# alarmclock6.net
KiCad netlist of a schematic drawn in EAGLE
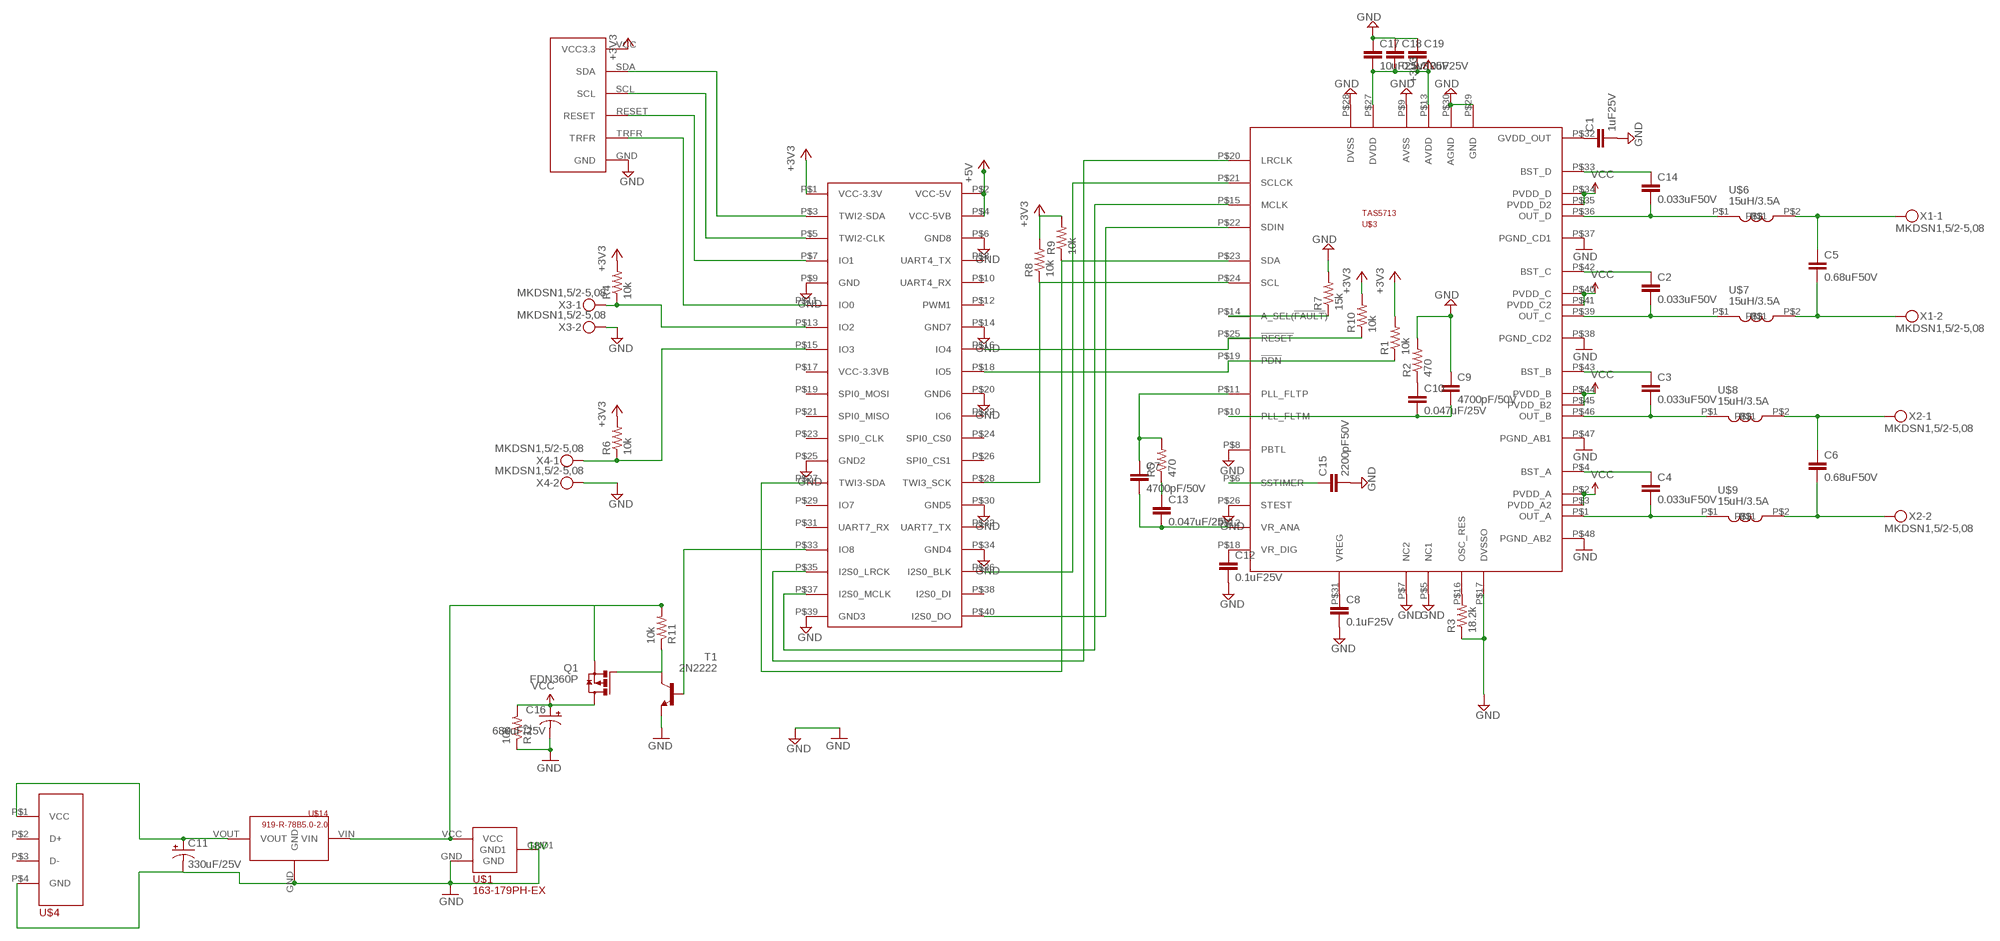
[diagram p0: schematic, sheet 1]

(export (version "E")
  (design (tool "Eeschema 10.0.6"))
  (components
    (comp (ref "C1")
      (value "1uF25V")
      (footprint "eagle-import:0603-CAP")
      (libsource (lib "eagle-import") (part "CAP0603-CAP"))
    )
    (comp (ref "C2")
      (value "0.033uF50V")
      (footprint "eagle-import:0603-CAP")
      (libsource (lib "eagle-import") (part "CAP0603-CAP"))
    )
    (comp (ref "C3")
      (value "0.033uF50V")
      (footprint "eagle-import:0603-CAP")
      (libsource (lib "eagle-import") (part "CAP0603-CAP"))
    )
    (comp (ref "C4")
      (value "0.033uF50V")
      (footprint "eagle-import:0603-CAP")
      (libsource (lib "eagle-import") (part "CAP0603-CAP"))
    )
    (comp (ref "C5")
      (value "0.68uF50V")
      (footprint "eagle-import:0603-CAP")
      (libsource (lib "eagle-import") (part "CAP0603-CAP"))
    )
    (comp (ref "C6")
      (value "0.68uF50V")
      (footprint "eagle-import:0603-CAP")
      (libsource (lib "eagle-import") (part "CAP0603-CAP"))
    )
    (comp (ref "C7")
      (value "4700pF/50V")
      (footprint "eagle-import:0603-CAP")
      (libsource (lib "eagle-import") (part "CAP0603-CAP"))
    )
    (comp (ref "C8")
      (value "0.1uF25V")
      (footprint "eagle-import:0603-CAP")
      (libsource (lib "eagle-import") (part "CAP0603-CAP"))
    )
    (comp (ref "C9")
      (value "4700pF/50V")
      (footprint "eagle-import:0603-CAP")
      (libsource (lib "eagle-import") (part "CAP0603-CAP"))
    )
    (comp (ref "C10")
      (value "0.047uF/25V")
      (footprint "eagle-import:0603-CAP")
      (libsource (lib "eagle-import") (part "CAP0603-CAP"))
    )
    (comp (ref "C11")
      (value "330uF/25V")
      (footprint "eagle-import:CPOL-RADIAL-10UF-25V")
      (libsource (lib "eagle-import") (part "CAP_POLPTH2"))
    )
    (comp (ref "C12")
      (value "0.1uF25V")
      (footprint "eagle-import:0603-CAP")
      (libsource (lib "eagle-import") (part "CAP0603-CAP"))
    )
    (comp (ref "C13")
      (value "0.047uF/25V")
      (footprint "eagle-import:0603-CAP")
      (libsource (lib "eagle-import") (part "CAP0603-CAP"))
    )
    (comp (ref "C14")
      (value "0.033uF50V")
      (footprint "eagle-import:0603-CAP")
      (libsource (lib "eagle-import") (part "CAP0603-CAP"))
    )
    (comp (ref "C15")
      (value "2200pF50V")
      (footprint "eagle-import:0603-CAP")
      (libsource (lib "eagle-import") (part "CAP0603-CAP"))
    )
    (comp (ref "C16")
      (value "680uF/25V")
      (footprint "eagle-import:CPOL-RADIAL-10UF-25V")
      (libsource (lib "eagle-import") (part "CAP_POLPTH2"))
    )
    (comp (ref "C17")
      (value "10uF25V")
      (footprint "eagle-import:0603-CAP")
      (libsource (lib "eagle-import") (part "CAP0603-CAP"))
    )
    (comp (ref "C18")
      (value "0.1uF25V")
      (footprint "eagle-import:0603-CAP")
      (libsource (lib "eagle-import") (part "CAP0603-CAP"))
    )
    (comp (ref "C19")
      (value "10uF25V")
      (footprint "eagle-import:0603-CAP")
      (libsource (lib "eagle-import") (part "CAP0603-CAP"))
    )
    (comp (ref "Q1")
      (value "FDN360P")
      (footprint "eagle-import:SUPER-SOT3")
      (libsource (lib "eagle-import") (part "FDN360P"))
    )
    (comp (ref "R1")
      (value "10k")
      (footprint "eagle-import:0603-RES")
      (libsource (lib "eagle-import") (part "RESISTOR0603-RES"))
    )
    (comp (ref "R2")
      (value "470")
      (footprint "eagle-import:0603-RES")
      (libsource (lib "eagle-import") (part "RESISTOR0603-RES"))
    )
    (comp (ref "R3")
      (value "18.2k")
      (footprint "eagle-import:0603-RES")
      (libsource (lib "eagle-import") (part "RESISTOR0603-RES"))
    )
    (comp (ref "R4")
      (value "10k")
      (footprint "eagle-import:0603-RES")
      (libsource (lib "eagle-import") (part "RESISTOR0603-RES"))
    )
    (comp (ref "R5")
      (value "470")
      (footprint "eagle-import:0603-RES")
      (libsource (lib "eagle-import") (part "RESISTOR0603-RES"))
    )
    (comp (ref "R6")
      (value "10k")
      (footprint "eagle-import:0603-RES")
      (libsource (lib "eagle-import") (part "RESISTOR0603-RES"))
    )
    (comp (ref "R7")
      (value "15k")
      (footprint "eagle-import:0603-RES")
      (libsource (lib "eagle-import") (part "RESISTOR0603-RES"))
    )
    (comp (ref "R8")
      (value "10k")
      (footprint "eagle-import:0603-RES")
      (libsource (lib "eagle-import") (part "RESISTOR0603-RES"))
    )
    (comp (ref "R9")
      (value "10k")
      (footprint "eagle-import:0603-RES")
      (libsource (lib "eagle-import") (part "RESISTOR0603-RES"))
    )
    (comp (ref "R10")
      (value "10k")
      (footprint "eagle-import:0603-RES")
      (libsource (lib "eagle-import") (part "RESISTOR0603-RES"))
    )
    (comp (ref "R11")
      (value "10k")
      (footprint "eagle-import:0603-RES")
      (libsource (lib "eagle-import") (part "RESISTOR0603-RES"))
    )
    (comp (ref "R12")
      (value "10k")
      (footprint "eagle-import:0603-RES")
      (libsource (lib "eagle-import") (part "RESISTOR0603-RES"))
    )
    (comp (ref "T1")
      (value "2N2222")
      (footprint "eagle-import:TO18")
      (libsource (lib "eagle-import") (part "2N2222"))
    )
    (comp (ref "U$1")
      (value "163-179PH-EX")
      (footprint "eagle-import:163-179PH-EX_DIM")
      (libsource (lib "eagle-import") (part "163-179PH-EX"))
    )
    (comp (ref "U$3")
      (value "TAS5713")
      (footprint "eagle-import:TAS5713_DIM")
      (libsource (lib "eagle-import") (part "TAS5713"))
    )
    (comp (ref "U$4")
      (value "USB_TYPEA_CONNECTOR")
      (footprint "eagle-import:USB_DIM")
      (libsource (lib "eagle-import") (part "USB_TYPEA_CONNECTOR"))
    )
    (comp (ref "U$5")
      (value "BANANAPRO-CON6")
      (footprint "eagle-import:BANANAPRO-CON6_DIM")
      (libsource (lib "eagle-import") (part "BANANAPRO-CON6"))
    )
    (comp (ref "U$6")
      (value "15uH/3.5A")
      (footprint "eagle-import:MSS1260_DIM")
      (libsource (lib "eagle-import") (part "MSS1260INDUCTOR"))
    )
    (comp (ref "U$7")
      (value "15uH/3.5A")
      (footprint "eagle-import:MSS1260_DIM")
      (libsource (lib "eagle-import") (part "MSS1260INDUCTOR"))
    )
    (comp (ref "U$8")
      (value "15uH/3.5A")
      (footprint "eagle-import:MSS1260_DIM")
      (libsource (lib "eagle-import") (part "MSS1260INDUCTOR"))
    )
    (comp (ref "U$9")
      (value "15uH/3.5A")
      (footprint "eagle-import:MSS1260_DIM")
      (libsource (lib "eagle-import") (part "MSS1260INDUCTOR"))
    )
    (comp (ref "U$10")
      (value "SKYWRITER")
      (footprint "eagle-import:SKYWRITER_DIM")
      (libsource (lib "eagle-import") (part "SKYWRITER"))
    )
    (comp (ref "U$14")
      (value "919-R-78B5.0-2.0")
      (footprint "eagle-import:919-R-78B5.0-2.0_DIM")
      (libsource (lib "eagle-import") (part "919-R-78B5.0-2.0"))
    )
    (comp (ref "X1")
      (value "MKDSN1,5/2-5,08")
      (footprint "eagle-import:MKDSN1,5_2-5,08")
      (libsource (lib "eagle-import") (part "MKDSN1,5/2-5,08"))
    )
    (comp (ref "X2")
      (value "MKDSN1,5/2-5,08")
      (footprint "eagle-import:MKDSN1,5_2-5,08")
      (libsource (lib "eagle-import") (part "MKDSN1,5/2-5,08"))
    )
    (comp (ref "X3")
      (value "MKDSN1,5/2-5,08")
      (footprint "eagle-import:MKDSN1,5_2-5,08")
      (libsource (lib "eagle-import") (part "MKDSN1,5/2-5,08"))
    )
    (comp (ref "X4")
      (value "MKDSN1,5/2-5,08")
      (footprint "eagle-import:MKDSN1,5_2-5,08")
      (libsource (lib "eagle-import") (part "MKDSN1,5/2-5,08"))
    )
  )
  (nets
    (net (code "1") (name "+3V3") (class "Default")
      (node (ref "C17") (pin "2") (pinfunction "2_2") (pintype "passive"))
      (node (ref "C18") (pin "2") (pinfunction "2_2") (pintype "passive"))
      (node (ref "C19") (pin "2") (pinfunction "2_2") (pintype "passive"))
      (node (ref "R1") (pin "2") (pinfunction "2_2") (pintype "passive"))
      (node (ref "R10") (pin "2") (pinfunction "2_2") (pintype "passive"))
      (node (ref "R4") (pin "2") (pinfunction "2_2") (pintype "passive"))
      (node (ref "R6") (pin "2") (pinfunction "2_2") (pintype "passive"))
      (node (ref "R8") (pin "2") (pinfunction "2_2") (pintype "passive"))
      (node (ref "R9") (pin "2") (pinfunction "2_2") (pintype "passive"))
      (node (ref "U$10") (pin "VCC") (pinfunction "VCC3.3_VCC") (pintype "bidirectional"))
      (node (ref "U$3") (pin "P$13") (pinfunction "AVDD_P$13") (pintype "bidirectional"))
      (node (ref "U$3") (pin "P$27") (pinfunction "DVDD_P$27") (pintype "bidirectional"))
      (node (ref "U$5") (pin "P$1") (pinfunction "VCC-3.3V_P$1") (pintype "bidirectional"))
    )
    (net (code "2") (name "+5V") (class "Default")
      (node (ref "U$5") (pin "P$2") (pinfunction "VCC-5V_P$2") (pintype "bidirectional"))
      (node (ref "U$5") (pin "P$4") (pinfunction "VCC-5VB_P$4") (pintype "bidirectional"))
    )
    (net (code "3") (name "GND") (class "Default")
      (node (ref "C1") (pin "2") (pinfunction "2_2") (pintype "passive"))
      (node (ref "C11") (pin "2") (pinfunction "-_2") (pintype "passive"))
      (node (ref "C12") (pin "2") (pinfunction "2_2") (pintype "passive"))
      (node (ref "C15") (pin "2") (pinfunction "2_2") (pintype "passive"))
      (node (ref "C16") (pin "2") (pinfunction "-_2") (pintype "passive"))
      (node (ref "C17") (pin "1") (pinfunction "1_1") (pintype "passive"))
      (node (ref "C18") (pin "1") (pinfunction "1_1") (pintype "passive"))
      (node (ref "C19") (pin "1") (pinfunction "1_1") (pintype "passive"))
      (node (ref "C8") (pin "2") (pinfunction "2_2") (pintype "passive"))
      (node (ref "C9") (pin "1") (pinfunction "1_1") (pintype "passive"))
      (node (ref "R12") (pin "1") (pinfunction "1_1") (pintype "passive"))
      (node (ref "R2") (pin "2") (pinfunction "2_2") (pintype "passive"))
      (node (ref "R3") (pin "1") (pinfunction "1_1") (pintype "passive"))
      (node (ref "R7") (pin "2") (pinfunction "2_2") (pintype "passive"))
      (node (ref "T1") (pin "1") (pinfunction "E_1") (pintype "passive"))
      (node (ref "U$1") (pin "GND") (pinfunction "GND_GND") (pintype "bidirectional"))
      (node (ref "U$1") (pin "GND1") (pinfunction "GND1_GND1") (pintype "bidirectional"))
      (node (ref "U$10") (pin "GND") (pinfunction "GND_GND") (pintype "bidirectional"))
      (node (ref "U$14") (pin "GND") (pinfunction "GND_GND") (pintype "bidirectional"))
      (node (ref "U$3") (pin "P$17") (pinfunction "DVSSO_P$17") (pintype "bidirectional"))
      (node (ref "U$3") (pin "P$26") (pinfunction "STEST_P$26") (pintype "bidirectional"))
      (node (ref "U$3") (pin "P$28") (pinfunction "DVSS_P$28") (pintype "bidirectional"))
      (node (ref "U$3") (pin "P$29") (pinfunction "GND_P$29") (pintype "bidirectional"))
      (node (ref "U$3") (pin "P$30") (pinfunction "AGND_P$30") (pintype "bidirectional"))
      (node (ref "U$3") (pin "P$37") (pinfunction "PGND_CD1_P$37") (pintype "bidirectional"))
      (node (ref "U$3") (pin "P$38") (pinfunction "PGND_CD2_P$38") (pintype "bidirectional"))
      (node (ref "U$3") (pin "P$47") (pinfunction "PGND_AB1_P$47") (pintype "bidirectional"))
      (node (ref "U$3") (pin "P$48") (pinfunction "PGND_AB2_P$48") (pintype "bidirectional"))
      (node (ref "U$3") (pin "P$5") (pinfunction "NC1_P$5") (pintype "bidirectional"))
      (node (ref "U$3") (pin "P$7") (pinfunction "NC2_P$7") (pintype "bidirectional"))
      (node (ref "U$3") (pin "P$8") (pinfunction "PBTL_P$8") (pintype "bidirectional"))
      (node (ref "U$3") (pin "P$9") (pinfunction "AVSS_P$9") (pintype "bidirectional"))
      (node (ref "U$4") (pin "P$4") (pinfunction "GND_P$4") (pintype "bidirectional"))
      (node (ref "U$5") (pin "P$14") (pinfunction "GND7_P$14") (pintype "bidirectional"))
      (node (ref "U$5") (pin "P$20") (pinfunction "GND6_P$20") (pintype "bidirectional"))
      (node (ref "U$5") (pin "P$25") (pinfunction "GND2_P$25") (pintype "bidirectional"))
      (node (ref "U$5") (pin "P$30") (pinfunction "GND5_P$30") (pintype "bidirectional"))
      (node (ref "U$5") (pin "P$34") (pinfunction "GND4_P$34") (pintype "bidirectional"))
      (node (ref "U$5") (pin "P$39") (pinfunction "GND3_P$39") (pintype "bidirectional"))
      (node (ref "U$5") (pin "P$6") (pinfunction "GND8_P$6") (pintype "bidirectional"))
      (node (ref "U$5") (pin "P$9") (pinfunction "GND_P$9") (pintype "bidirectional"))
      (node (ref "X3") (pin "2") (pinfunction "KL_2") (pintype "passive"))
      (node (ref "X4") (pin "2") (pinfunction "KL_2") (pintype "passive"))
    )
    (net (code "4") (name "Net-(C10-Pad1)") (class "Default")
      (node (ref "C10") (pin "1") (pinfunction "1_1") (pintype "passive"))
      (node (ref "R2") (pin "1") (pinfunction "1_1") (pintype "passive"))
    )
    (net (code "5") (name "Net-(C11-+)") (class "Default")
      (node (ref "C11") (pin "1") (pinfunction "+_1") (pintype "passive"))
      (node (ref "U$14") (pin "VOUT") (pinfunction "VOUT_VOUT") (pintype "bidirectional"))
      (node (ref "U$4") (pin "P$1") (pinfunction "VCC_P$1") (pintype "bidirectional"))
    )
    (net (code "6") (name "Net-(C13-Pad1)") (class "Default")
      (node (ref "C13") (pin "1") (pinfunction "1_1") (pintype "passive"))
      (node (ref "R5") (pin "1") (pinfunction "1_1") (pintype "passive"))
    )
    (net (code "7") (name "Net-(Q1-G)") (class "Default")
      (node (ref "Q1") (pin "1") (pinfunction "G_1") (pintype "passive"))
      (node (ref "R11") (pin "1") (pinfunction "1_1") (pintype "passive"))
      (node (ref "T1") (pin "3") (pinfunction "C_3") (pintype "passive"))
    )
    (net (code "8") (name "Net-(Q1-S)") (class "Default")
      (node (ref "Q1") (pin "2") (pinfunction "S_2") (pintype "passive"))
      (node (ref "R11") (pin "2") (pinfunction "2_2") (pintype "passive"))
      (node (ref "U$1") (pin "VCC") (pinfunction "VCC_VCC") (pintype "bidirectional"))
      (node (ref "U$14") (pin "VIN") (pinfunction "VIN_VIN") (pintype "bidirectional"))
    )
    (net (code "9") (name "Net-(T1-B)") (class "Default")
      (node (ref "T1") (pin "2") (pinfunction "B_2") (pintype "passive"))
      (node (ref "U$5") (pin "P$33") (pinfunction "IO8_P$33") (pintype "bidirectional"))
    )
    (net (code "10") (name "Net-(U$3-A_SEL(~{FAULT}))") (class "Default")
      (node (ref "R7") (pin "1") (pinfunction "1_1") (pintype "passive"))
      (node (ref "U$3") (pin "P$14") (pinfunction "A_SEL(~{FAULT})_P$14") (pintype "bidirectional"))
    )
    (net (code "11") (name "Net-(U$3-BST_A)") (class "Default")
      (node (ref "C4") (pin "1") (pinfunction "1_1") (pintype "passive"))
      (node (ref "U$3") (pin "P$4") (pinfunction "BST_A_P$4") (pintype "bidirectional"))
    )
    (net (code "12") (name "Net-(U$3-BST_B)") (class "Default")
      (node (ref "C3") (pin "1") (pinfunction "1_1") (pintype "passive"))
      (node (ref "U$3") (pin "P$43") (pinfunction "BST_B_P$43") (pintype "bidirectional"))
    )
    (net (code "13") (name "Net-(U$3-BST_C)") (class "Default")
      (node (ref "C2") (pin "1") (pinfunction "1_1") (pintype "passive"))
      (node (ref "U$3") (pin "P$42") (pinfunction "BST_C_P$42") (pintype "bidirectional"))
    )
    (net (code "14") (name "Net-(U$3-BST_D)") (class "Default")
      (node (ref "C14") (pin "1") (pinfunction "1_1") (pintype "passive"))
      (node (ref "U$3") (pin "P$33") (pinfunction "BST_D_P$33") (pintype "bidirectional"))
    )
    (net (code "15") (name "Net-(U$3-GVDD_OUT)") (class "Default")
      (node (ref "C1") (pin "1") (pinfunction "1_1") (pintype "passive"))
      (node (ref "U$3") (pin "P$32") (pinfunction "GVDD_OUT_P$32") (pintype "bidirectional"))
    )
    (net (code "16") (name "Net-(U$3-LRCLK)") (class "Default")
      (node (ref "U$3") (pin "P$20") (pinfunction "LRCLK_P$20") (pintype "bidirectional"))
      (node (ref "U$5") (pin "P$35") (pinfunction "I2S0_LRCK_P$35") (pintype "bidirectional"))
    )
    (net (code "17") (name "Net-(U$3-MCLK)") (class "Default")
      (node (ref "U$3") (pin "P$15") (pinfunction "MCLK_P$15") (pintype "bidirectional"))
      (node (ref "U$5") (pin "P$37") (pinfunction "I2S0_MCLK_P$37") (pintype "bidirectional"))
    )
    (net (code "18") (name "Net-(U$3-OSC_RES)") (class "Default")
      (node (ref "R3") (pin "2") (pinfunction "2_2") (pintype "passive"))
      (node (ref "U$3") (pin "P$16") (pinfunction "OSC_RES_P$16") (pintype "bidirectional"))
    )
    (net (code "19") (name "Net-(U$3-OUT_A)") (class "Default")
      (node (ref "C4") (pin "2") (pinfunction "2_2") (pintype "passive"))
      (node (ref "U$3") (pin "P$1") (pinfunction "OUT_A_P$1") (pintype "bidirectional"))
      (node (ref "U$9") (pin "P$1") (pinfunction "P$1_P$1") (pintype "bidirectional"))
    )
    (net (code "20") (name "Net-(U$3-OUT_B)") (class "Default")
      (node (ref "C3") (pin "2") (pinfunction "2_2") (pintype "passive"))
      (node (ref "U$3") (pin "P$46") (pinfunction "OUT_B_P$46") (pintype "bidirectional"))
      (node (ref "U$8") (pin "P$1") (pinfunction "P$1_P$1") (pintype "bidirectional"))
    )
    (net (code "21") (name "Net-(U$3-OUT_C)") (class "Default")
      (node (ref "C2") (pin "2") (pinfunction "2_2") (pintype "passive"))
      (node (ref "U$3") (pin "P$39") (pinfunction "OUT_C_P$39") (pintype "bidirectional"))
      (node (ref "U$7") (pin "P$1") (pinfunction "P$1_P$1") (pintype "bidirectional"))
    )
    (net (code "22") (name "Net-(U$3-OUT_D)") (class "Default")
      (node (ref "C14") (pin "2") (pinfunction "2_2") (pintype "passive"))
      (node (ref "U$3") (pin "P$36") (pinfunction "OUT_D_P$36") (pintype "bidirectional"))
      (node (ref "U$6") (pin "P$1") (pinfunction "P$1_P$1") (pintype "bidirectional"))
    )
    (net (code "23") (name "Net-(U$3-PLL_FLTM)") (class "Default")
      (node (ref "C10") (pin "2") (pinfunction "2_2") (pintype "passive"))
      (node (ref "C9") (pin "2") (pinfunction "2_2") (pintype "passive"))
      (node (ref "U$3") (pin "P$10") (pinfunction "PLL_FLTM_P$10") (pintype "bidirectional"))
    )
    (net (code "24") (name "Net-(U$3-PLL_FLTP)") (class "Default")
      (node (ref "C7") (pin "1") (pinfunction "1_1") (pintype "passive"))
      (node (ref "R5") (pin "2") (pinfunction "2_2") (pintype "passive"))
      (node (ref "U$3") (pin "P$11") (pinfunction "PLL_FLTP_P$11") (pintype "bidirectional"))
    )
    (net (code "25") (name "Net-(U$3-SCL)") (class "Default")
      (node (ref "R8") (pin "1") (pinfunction "1_1") (pintype "passive"))
      (node (ref "U$3") (pin "P$24") (pinfunction "SCL_P$24") (pintype "bidirectional"))
      (node (ref "U$5") (pin "P$28") (pinfunction "TWI3_SCK_P$28") (pintype "bidirectional"))
    )
    (net (code "26") (name "Net-(U$3-SCLCK)") (class "Default")
      (node (ref "U$3") (pin "P$21") (pinfunction "SCLCK_P$21") (pintype "bidirectional"))
      (node (ref "U$5") (pin "P$36") (pinfunction "I2S0_BLK_P$36") (pintype "bidirectional"))
    )
    (net (code "27") (name "Net-(U$3-SDA)") (class "Default")
      (node (ref "R9") (pin "1") (pinfunction "1_1") (pintype "passive"))
      (node (ref "U$3") (pin "P$23") (pinfunction "SDA_P$23") (pintype "bidirectional"))
      (node (ref "U$5") (pin "P$27") (pinfunction "TWI3-SDA_P$27") (pintype "bidirectional"))
    )
    (net (code "28") (name "Net-(U$3-SDIN)") (class "Default")
      (node (ref "U$3") (pin "P$22") (pinfunction "SDIN_P$22") (pintype "bidirectional"))
      (node (ref "U$5") (pin "P$40") (pinfunction "I2S0_DO_P$40") (pintype "bidirectional"))
    )
    (net (code "29") (name "Net-(U$3-SSTIMER)") (class "Default")
      (node (ref "C15") (pin "1") (pinfunction "1_1") (pintype "passive"))
      (node (ref "U$3") (pin "P$6") (pinfunction "SSTIMER_P$6") (pintype "bidirectional"))
    )
    (net (code "30") (name "Net-(U$3-VREG)") (class "Default")
      (node (ref "C8") (pin "1") (pinfunction "1_1") (pintype "passive"))
      (node (ref "U$3") (pin "P$31") (pinfunction "VREG_P$31") (pintype "bidirectional"))
    )
    (net (code "31") (name "Net-(U$3-VR_ANA)") (class "Default")
      (node (ref "C13") (pin "2") (pinfunction "2_2") (pintype "passive"))
      (node (ref "C7") (pin "2") (pinfunction "2_2") (pintype "passive"))
      (node (ref "U$3") (pin "P$12") (pinfunction "VR_ANA_P$12") (pintype "bidirectional"))
    )
    (net (code "32") (name "Net-(U$3-VR_DIG)") (class "Default")
      (node (ref "C12") (pin "1") (pinfunction "1_1") (pintype "passive"))
      (node (ref "U$3") (pin "P$18") (pinfunction "VR_DIG_P$18") (pintype "bidirectional"))
    )
    (net (code "33") (name "Net-(U$3-~{PDN})") (class "Default")
      (node (ref "R1") (pin "1") (pinfunction "1_1") (pintype "passive"))
      (node (ref "U$3") (pin "P$19") (pinfunction "~{PDN}_P$19") (pintype "bidirectional"))
      (node (ref "U$5") (pin "P$18") (pinfunction "IO5_P$18") (pintype "bidirectional"))
    )
    (net (code "34") (name "Net-(U$3-~{RESET})") (class "Default")
      (node (ref "R10") (pin "1") (pinfunction "1_1") (pintype "passive"))
      (node (ref "U$3") (pin "P$25") (pinfunction "~{RESET}_P$25") (pintype "bidirectional"))
      (node (ref "U$5") (pin "P$16") (pinfunction "IO4_P$16") (pintype "bidirectional"))
    )
    (net (code "35") (name "Net-(U$5-IO0)") (class "Default")
      (node (ref "U$10") (pin "TRFR") (pinfunction "TRFR_TRFR") (pintype "bidirectional"))
      (node (ref "U$5") (pin "P$11") (pinfunction "IO0_P$11") (pintype "bidirectional"))
    )
    (net (code "36") (name "Net-(U$5-IO1)") (class "Default")
      (node (ref "U$10") (pin "RESET") (pinfunction "RESET_RESET") (pintype "bidirectional"))
      (node (ref "U$5") (pin "P$7") (pinfunction "IO1_P$7") (pintype "bidirectional"))
    )
    (net (code "37") (name "Net-(U$5-IO2)") (class "Default")
      (node (ref "R4") (pin "1") (pinfunction "1_1") (pintype "passive"))
      (node (ref "U$5") (pin "P$13") (pinfunction "IO2_P$13") (pintype "bidirectional"))
      (node (ref "X3") (pin "1") (pinfunction "KL_1") (pintype "passive"))
    )
    (net (code "38") (name "Net-(U$5-IO3)") (class "Default")
      (node (ref "R6") (pin "1") (pinfunction "1_1") (pintype "passive"))
      (node (ref "U$5") (pin "P$15") (pinfunction "IO3_P$15") (pintype "bidirectional"))
      (node (ref "X4") (pin "1") (pinfunction "KL_1") (pintype "passive"))
    )
    (net (code "39") (name "Net-(U$5-TWI2-CLK)") (class "Default")
      (node (ref "U$10") (pin "SCL") (pinfunction "SCL_SCL") (pintype "bidirectional"))
      (node (ref "U$5") (pin "P$5") (pinfunction "TWI2-CLK_P$5") (pintype "bidirectional"))
    )
    (net (code "40") (name "Net-(U$5-TWI2-SDA)") (class "Default")
      (node (ref "U$10") (pin "SDA") (pinfunction "SDA_SDA") (pintype "bidirectional"))
      (node (ref "U$5") (pin "P$3") (pinfunction "TWI2-SDA_P$3") (pintype "bidirectional"))
    )
    (net (code "41") (name "Net-(X1A-KL)") (class "Default")
      (node (ref "C5") (pin "1") (pinfunction "1_1") (pintype "passive"))
      (node (ref "U$6") (pin "P$2") (pinfunction "P$2_P$2") (pintype "bidirectional"))
      (node (ref "X1") (pin "1") (pinfunction "KL_1") (pintype "passive"))
    )
    (net (code "42") (name "Net-(X1B-KL)") (class "Default")
      (node (ref "C5") (pin "2") (pinfunction "2_2") (pintype "passive"))
      (node (ref "U$7") (pin "P$2") (pinfunction "P$2_P$2") (pintype "bidirectional"))
      (node (ref "X1") (pin "2") (pinfunction "KL_2") (pintype "passive"))
    )
    (net (code "43") (name "Net-(X2A-KL)") (class "Default")
      (node (ref "C6") (pin "1") (pinfunction "1_1") (pintype "passive"))
      (node (ref "U$8") (pin "P$2") (pinfunction "P$2_P$2") (pintype "bidirectional"))
      (node (ref "X2") (pin "1") (pinfunction "KL_1") (pintype "passive"))
    )
    (net (code "44") (name "Net-(X2B-KL)") (class "Default")
      (node (ref "C6") (pin "2") (pinfunction "2_2") (pintype "passive"))
      (node (ref "U$9") (pin "P$2") (pinfunction "P$2_P$2") (pintype "bidirectional"))
      (node (ref "X2") (pin "2") (pinfunction "KL_2") (pintype "passive"))
    )
    (net (code "45") (name "VCC") (class "Default")
      (node (ref "C16") (pin "1") (pinfunction "+_1") (pintype "passive"))
      (node (ref "Q1") (pin "3") (pinfunction "D_3") (pintype "passive"))
      (node (ref "R12") (pin "2") (pinfunction "2_2") (pintype "passive"))
      (node (ref "U$3") (pin "P$2") (pinfunction "PVDD_A_P$2") (pintype "bidirectional"))
      (node (ref "U$3") (pin "P$3") (pinfunction "PVDD_A2_P$3") (pintype "bidirectional"))
      (node (ref "U$3") (pin "P$34") (pinfunction "PVDD_D_P$34") (pintype "bidirectional"))
      (node (ref "U$3") (pin "P$35") (pinfunction "PVDD_D2_P$35") (pintype "bidirectional"))
      (node (ref "U$3") (pin "P$40") (pinfunction "PVDD_C_P$40") (pintype "bidirectional"))
      (node (ref "U$3") (pin "P$41") (pinfunction "PVDD_C2_P$41") (pintype "bidirectional"))
      (node (ref "U$3") (pin "P$44") (pinfunction "PVDD_B_P$44") (pintype "bidirectional"))
      (node (ref "U$3") (pin "P$45") (pinfunction "PVDD_B2_P$45") (pintype "bidirectional"))
    )
    (net (code "46") (name "unconnected-(U$4-D+-PadP$2)") (class "Default")
      (node (ref "U$4") (pin "P$2") (pinfunction "D+_P$2") (pintype "bidirectional"))
    )
    (net (code "47") (name "unconnected-(U$4-D--PadP$3)") (class "Default")
      (node (ref "U$4") (pin "P$3") (pinfunction "D-_P$3") (pintype "bidirectional"))
    )
    (net (code "48") (name "unconnected-(U$5-I2S0_DI-PadP$38)") (class "Default")
      (node (ref "U$5") (pin "P$38") (pinfunction "I2S0_DI_P$38") (pintype "bidirectional"))
    )
    (net (code "49") (name "unconnected-(U$5-IO6-PadP$22)") (class "Default")
      (node (ref "U$5") (pin "P$22") (pinfunction "IO6_P$22") (pintype "bidirectional"))
    )
    (net (code "50") (name "unconnected-(U$5-IO7-PadP$29)") (class "Default")
      (node (ref "U$5") (pin "P$29") (pinfunction "IO7_P$29") (pintype "bidirectional"))
    )
    (net (code "51") (name "unconnected-(U$5-PWM1-PadP$12)") (class "Default")
      (node (ref "U$5") (pin "P$12") (pinfunction "PWM1_P$12") (pintype "bidirectional"))
    )
    (net (code "52") (name "unconnected-(U$5-SPI0_CLK-PadP$23)") (class "Default")
      (node (ref "U$5") (pin "P$23") (pinfunction "SPI0_CLK_P$23") (pintype "bidirectional"))
    )
    (net (code "53") (name "unconnected-(U$5-SPI0_CS0-PadP$24)") (class "Default")
      (node (ref "U$5") (pin "P$24") (pinfunction "SPI0_CS0_P$24") (pintype "bidirectional"))
    )
    (net (code "54") (name "unconnected-(U$5-SPI0_CS1-PadP$26)") (class "Default")
      (node (ref "U$5") (pin "P$26") (pinfunction "SPI0_CS1_P$26") (pintype "bidirectional"))
    )
    (net (code "55") (name "unconnected-(U$5-SPI0_MISO-PadP$21)") (class "Default")
      (node (ref "U$5") (pin "P$21") (pinfunction "SPI0_MISO_P$21") (pintype "bidirectional"))
    )
    (net (code "56") (name "unconnected-(U$5-SPI0_MOSI-PadP$19)") (class "Default")
      (node (ref "U$5") (pin "P$19") (pinfunction "SPI0_MOSI_P$19") (pintype "bidirectional"))
    )
    (net (code "57") (name "unconnected-(U$5-UART4_RX-PadP$10)") (class "Default")
      (node (ref "U$5") (pin "P$10") (pinfunction "UART4_RX_P$10") (pintype "bidirectional"))
    )
    (net (code "58") (name "unconnected-(U$5-UART4_TX-PadP$8)") (class "Default")
      (node (ref "U$5") (pin "P$8") (pinfunction "UART4_TX_P$8") (pintype "bidirectional"))
    )
    (net (code "59") (name "unconnected-(U$5-UART7_RX-PadP$31)") (class "Default")
      (node (ref "U$5") (pin "P$31") (pinfunction "UART7_RX_P$31") (pintype "bidirectional"))
    )
    (net (code "60") (name "unconnected-(U$5-UART7_TX-PadP$32)") (class "Default")
      (node (ref "U$5") (pin "P$32") (pinfunction "UART7_TX_P$32") (pintype "bidirectional"))
    )
    (net (code "61") (name "unconnected-(U$5-VCC-3.3VB-PadP$17)") (class "Default")
      (node (ref "U$5") (pin "P$17") (pinfunction "VCC-3.3VB_P$17") (pintype "bidirectional"))
    )
  )
)
